# LMS7002M_EEPROM.net
KiCad netlist of a schematic drawn in Altium Designer
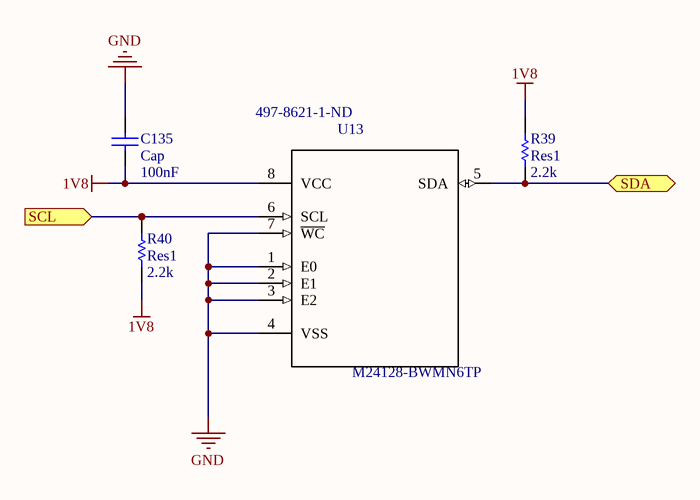
[diagram p0: LMS7002M EEPROM.SchDoc]

(export (version "E")
  (design (tool "Eeschema 10.0.6"))
  (components
    (comp (ref "C135")
      (value "Cap")
      (footprint "0402-A")
      (description "Capacitor")
      (fields (field (name "ALTIUM_VALUE") "100nF") (field (name "PUBLISHER") "Altium Limited"))
      (libsource (lib "Miscellaneous Devices") (part "Cap"))
    )
    (comp (ref "R39")
      (value "Res1")
      (footprint "0402-A")
      (description "Resistor")
      (fields (field (name "ALTIUM_VALUE") "2.2k") (field (name "PUBLISHER") "Altium Limited"))
      (libsource (lib "Miscellaneous Devices") (part "Res1"))
    )
    (comp (ref "R40")
      (value "Res1")
      (footprint "0402-A")
      (description "Resistor")
      (fields (field (name "ALTIUM_VALUE") "2.2k") (field (name "PUBLISHER") "Altium Limited"))
      (libsource (lib "Miscellaneous Devices") (part "Res1"))
    )
    (comp (ref "U13")
      (value "M24128-BWMN6TP")
      (footprint "*SOIC127P600X175-8N")
      (fields
        (field (name "BUYPART") "https://www.snapeda.com/parts/M24128-BWMN6TP/STMicroelectronics/view-part/1043181/?ref=eda")
        (field (name "SUPPLIER PART NUMBER 1") "497-8621-1-ND")
      )
      (libsource (lib "M24128-BWMN6TP") (part "M24128-BWMN6TP"))
    )
  )
  (nets
    (net (code "1") (name "/SCL") (class "Default")
      (node (ref "R40") (pin "2") (pinfunction "2_2") (pintype "passive"))
      (node (ref "U13") (pin "6") (pinfunction "SCL_6") (pintype "input"))
    )
    (net (code "2") (name "/SDA") (class "Default")
      (node (ref "R39") (pin "1") (pinfunction "1_1") (pintype "passive"))
      (node (ref "U13") (pin "5") (pinfunction "SDA_5") (pintype "bidirectional"))
    )
    (net (code "3") (name "1V8") (class "Default")
      (node (ref "C135") (pin "1") (pinfunction "1_1") (pintype "passive"))
      (node (ref "R39") (pin "2") (pinfunction "2_2") (pintype "passive"))
      (node (ref "R40") (pin "1") (pinfunction "1_1") (pintype "passive"))
      (node (ref "U13") (pin "8") (pinfunction "VCC_8") (pintype "power_in"))
    )
    (net (code "4") (name "GND") (class "Default")
      (node (ref "C135") (pin "2") (pinfunction "2_2") (pintype "passive"))
      (node (ref "U13") (pin "1") (pinfunction "E0_1") (pintype "input"))
      (node (ref "U13") (pin "2") (pinfunction "E1_2") (pintype "input"))
      (node (ref "U13") (pin "3") (pinfunction "E2_3") (pintype "input"))
      (node (ref "U13") (pin "4") (pinfunction "VSS_4") (pintype "passive"))
      (node (ref "U13") (pin "7") (pinfunction "~{WC}_7") (pintype "input"))
    )
  )
)
